# DDS.net
KiCad netlist of a schematic drawn in Altium Designer
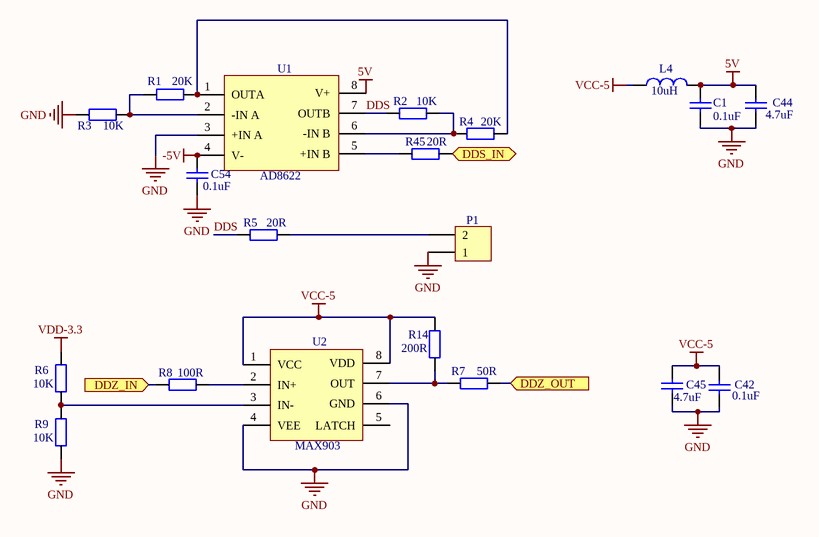
[diagram p0: DDS.SchDoc]

(export (version "E")
  (design (tool "Eeschema 10.0.6"))
  (components
    (comp (ref "C1")
      (value "0.1uF")
      (footprint "0603")
      (fields (field (name "Comment") "Capacitor-0603"))
      (libsource (lib "原理图库") (part "Capacitor-0603"))
    )
    (comp (ref "C42")
      (value "0.1uF")
      (footprint "0603")
      (fields (field (name "Comment") "Capacitor-0603"))
      (libsource (lib "原理图库") (part "Capacitor-0603"))
    )
    (comp (ref "C44")
      (value "4.7uF")
      (footprint "0603")
      (fields (field (name "Comment") "Capacitor-0603"))
      (libsource (lib "原理图库") (part "Capacitor-0603"))
    )
    (comp (ref "C45")
      (value "4.7uF")
      (footprint "0603")
      (fields (field (name "Comment") "Capacitor-0603"))
      (libsource (lib "原理图库") (part "Capacitor-0603"))
    )
    (comp (ref "C54")
      (value "0.1uF")
      (footprint "0603")
      (fields (field (name "Comment") "Capacitor-0603"))
      (libsource (lib "原理图库") (part "Capacitor-0603"))
    )
    (comp (ref "L4")
      (value "10uH")
      (footprint "0805")
      (fields (field (name "Comment") "Inductor"))
      (libsource (lib "原理图库") (part "Inductor"))
    )
    (comp (ref "P1") (value "端子") (footprint "2MM接线端子") (libsource (lib "原理图库") (part "端子")))
    (comp (ref "R1")
      (value "20K")
      (footprint "0603")
      (fields (field (name "Comment") "Resistor-0603"))
      (libsource (lib "原理图库") (part "Resistor-0603"))
    )
    (comp (ref "R2")
      (value "10K")
      (footprint "0603")
      (fields (field (name "Comment") "Resistor-0603"))
      (libsource (lib "原理图库") (part "Resistor-0603"))
    )
    (comp (ref "R3")
      (value "10K")
      (footprint "0603")
      (fields (field (name "Comment") "Resistor-0603"))
      (libsource (lib "原理图库") (part "Resistor-0603"))
    )
    (comp (ref "R4")
      (value "20K")
      (footprint "0603")
      (fields (field (name "Comment") "Resistor-0603"))
      (libsource (lib "原理图库") (part "Resistor-0603"))
    )
    (comp (ref "R5")
      (value "20R")
      (footprint "0603")
      (fields (field (name "Comment") "Resistor-0603"))
      (libsource (lib "原理图库") (part "Resistor-0603"))
    )
    (comp (ref "R6")
      (value "10K")
      (footprint "0603")
      (fields (field (name "Comment") "Resistor-0805"))
      (libsource (lib "原理图库") (part "Resistor-0805"))
    )
    (comp (ref "R7")
      (value "50R")
      (footprint "0603")
      (fields (field (name "Comment") "Resistor-0603"))
      (libsource (lib "原理图库") (part "Resistor-0603"))
    )
    (comp (ref "R8")
      (value "100R")
      (footprint "0603")
      (fields (field (name "Comment") "Resistor-0603"))
      (libsource (lib "原理图库") (part "Resistor-0603"))
    )
    (comp (ref "R9")
      (value "10K")
      (footprint "0603")
      (fields (field (name "Comment") "Resistor-0805"))
      (libsource (lib "原理图库") (part "Resistor-0805"))
    )
    (comp (ref "R14")
      (value "200R")
      (footprint "0603")
      (fields (field (name "Comment") "Resistor-0603"))
      (libsource (lib "") (part "Resistor-0603_1"))
    )
    (comp (ref "R45")
      (value "20R")
      (footprint "0603")
      (fields (field (name "Comment") "Resistor-0603"))
      (libsource (lib "原理图库") (part "Resistor-0603"))
    )
    (comp (ref "U1")
      (value "AD8622")
      (footprint "LM358-D")
      (fields (field (name "NAME") "AD8622"))
      (libsource (lib "原理图库") (part "AD8622"))
    )
    (comp (ref "U2")
      (value "MAX903")
      (footprint "LM358-D")
      (fields (field (name "NAME") "MAX903"))
      (libsource (lib "原理图库") (part "MAX903"))
    )
  )
  (nets
    (net (code "1") (name "-5V") (class "Default")
      (node (ref "C54") (pin "1") (pinfunction "1_1") (pintype "passive"))
      (node (ref "U1") (pin "4") (pinfunction "V-_4") (pintype "passive"))
    )
    (net (code "2") (name "/DDS") (class "Default")
      (node (ref "R2") (pin "2") (pinfunction "2_2") (pintype "passive"))
      (node (ref "R5") (pin "2") (pinfunction "2_2") (pintype "passive"))
      (node (ref "U1") (pin "7") (pinfunction "OUTB_7") (pintype "passive"))
    )
    (net (code "3") (name "/DDS_IN") (class "Default")
      (node (ref "R45") (pin "1") (pinfunction "1_1") (pintype "passive"))
    )
    (net (code "4") (name "/DDZ_IN") (class "Default")
      (node (ref "R8") (pin "2") (pinfunction "2_2") (pintype "passive"))
    )
    (net (code "5") (name "/DDZ_OUT") (class "Default")
      (node (ref "R7") (pin "1") (pinfunction "1_1") (pintype "passive"))
    )
    (net (code "6") (name "5V") (class "Default")
      (node (ref "C1") (pin "1") (pinfunction "1_1") (pintype "passive"))
      (node (ref "C44") (pin "1") (pinfunction "1_1") (pintype "passive"))
      (node (ref "L4") (pin "2") (pinfunction "2_2") (pintype "passive"))
      (node (ref "U1") (pin "8") (pinfunction "V+_8") (pintype "passive"))
    )
    (net (code "7") (name "GND") (class "Default")
      (node (ref "C1") (pin "2") (pinfunction "2_2") (pintype "passive"))
      (node (ref "C42") (pin "2") (pinfunction "2_2") (pintype "passive"))
      (node (ref "C44") (pin "2") (pinfunction "2_2") (pintype "passive"))
      (node (ref "C45") (pin "2") (pinfunction "2_2") (pintype "passive"))
      (node (ref "C54") (pin "2") (pinfunction "2_2") (pintype "passive"))
      (node (ref "P1") (pin "1") (pinfunction "1_1") (pintype "passive"))
      (node (ref "R3") (pin "2") (pinfunction "2_2") (pintype "passive"))
      (node (ref "R9") (pin "1") (pinfunction "1_1") (pintype "passive"))
      (node (ref "U1") (pin "3") (pinfunction "+IN_A_3") (pintype "passive"))
      (node (ref "U2") (pin "4") (pinfunction "VEE_4") (pintype "passive"))
      (node (ref "U2") (pin "6") (pinfunction "GND_6") (pintype "passive"))
    )
    (net (code "8") (name "Net-(P1-Pad2)") (class "Default")
      (node (ref "P1") (pin "2") (pinfunction "2_2") (pintype "passive"))
      (node (ref "R5") (pin "1") (pinfunction "1_1") (pintype "passive"))
    )
    (net (code "9") (name "Net-(U1-+IN_B)") (class "Default")
      (node (ref "R45") (pin "2") (pinfunction "2_2") (pintype "passive"))
      (node (ref "U1") (pin "5") (pinfunction "+IN_B_5") (pintype "passive"))
    )
    (net (code "10") (name "Net-(U1--IN_A)") (class "Default")
      (node (ref "R1") (pin "2") (pinfunction "2_2") (pintype "passive"))
      (node (ref "R3") (pin "1") (pinfunction "1_1") (pintype "passive"))
      (node (ref "U1") (pin "2") (pinfunction "-IN_A_2") (pintype "passive"))
    )
    (net (code "11") (name "Net-(U1--IN_B)") (class "Default")
      (node (ref "R2") (pin "1") (pinfunction "1_1") (pintype "passive"))
      (node (ref "R4") (pin "2") (pinfunction "2_2") (pintype "passive"))
      (node (ref "U1") (pin "6") (pinfunction "-IN_B_6") (pintype "passive"))
    )
    (net (code "12") (name "Net-(U1-OUTA)") (class "Default")
      (node (ref "R1") (pin "1") (pinfunction "1_1") (pintype "passive"))
      (node (ref "R4") (pin "1") (pinfunction "1_1") (pintype "passive"))
      (node (ref "U1") (pin "1") (pinfunction "OUTA_1") (pintype "passive"))
    )
    (net (code "13") (name "Net-(U2-IN+)") (class "Default")
      (node (ref "R8") (pin "1") (pinfunction "1_1") (pintype "passive"))
      (node (ref "U2") (pin "2") (pinfunction "IN+_2") (pintype "passive"))
    )
    (net (code "14") (name "Net-(U2-IN-)") (class "Default")
      (node (ref "R6") (pin "1") (pinfunction "1_1") (pintype "passive"))
      (node (ref "R9") (pin "2") (pinfunction "2_2") (pintype "passive"))
      (node (ref "U2") (pin "3") (pinfunction "IN-_3") (pintype "passive"))
    )
    (net (code "15") (name "Net-(U2-OUT)") (class "Default")
      (node (ref "R14") (pin "2") (pinfunction "2_2") (pintype "passive"))
      (node (ref "R7") (pin "2") (pinfunction "2_2") (pintype "passive"))
      (node (ref "U2") (pin "7") (pinfunction "OUT_7") (pintype "passive"))
    )
    (net (code "16") (name "VCC-5") (class "Default")
      (node (ref "C42") (pin "1") (pinfunction "1_1") (pintype "passive"))
      (node (ref "C45") (pin "1") (pinfunction "1_1") (pintype "passive"))
      (node (ref "L4") (pin "1") (pinfunction "1_1") (pintype "passive"))
      (node (ref "R14") (pin "1") (pinfunction "1_1") (pintype "passive"))
      (node (ref "U2") (pin "1") (pinfunction "VCC_1") (pintype "passive"))
      (node (ref "U2") (pin "8") (pinfunction "VDD_8") (pintype "passive"))
    )
    (net (code "17") (name "VDD-3.3") (class "Default")
      (node (ref "R6") (pin "2") (pinfunction "2_2") (pintype "passive"))
    )
    (net (code "18") (name "unconnected-(U2-LATCH-Pad5)") (class "Default")
      (node (ref "U2") (pin "5") (pinfunction "LATCH_5") (pintype "passive"))
    )
  )
)
